# Mezzanine_Connectors.net
KiCad netlist of a schematic drawn in Altium Designer
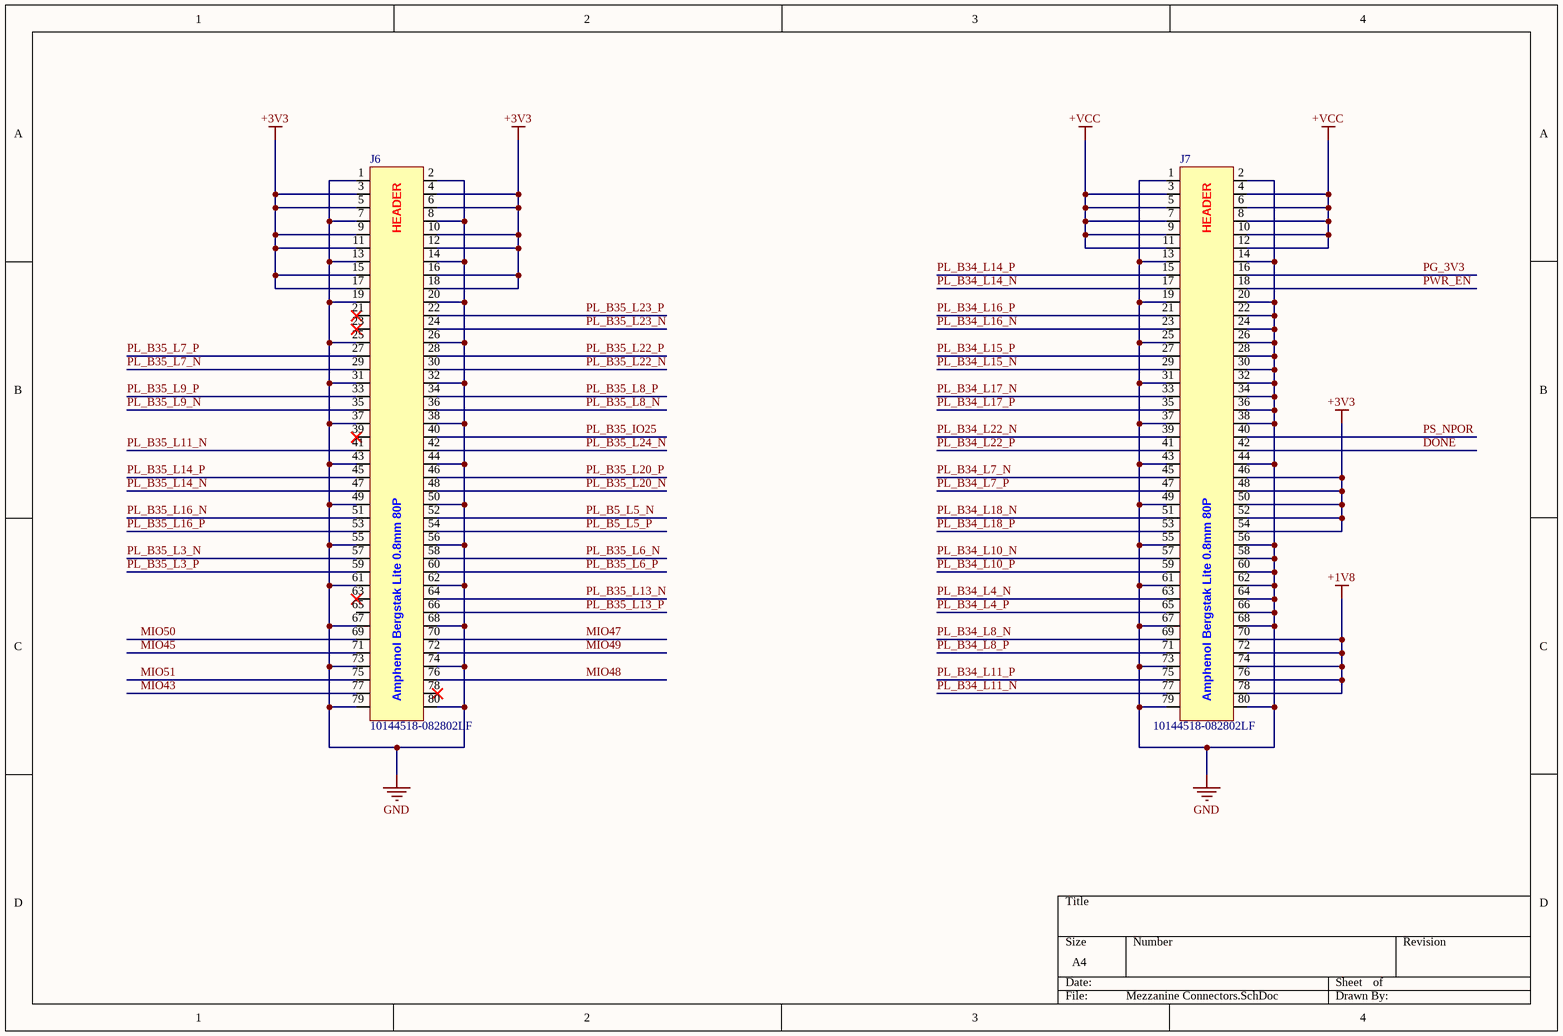
[diagram p0: Mezzanine Connectors.SchDoc]

(export (version "E")
  (design (tool "Eeschema 10.0.6"))
  (components
    (comp (ref "J6")
      (value "10144518-082802LF")
      (footprint "10144518-082802LF")
      (description "BergStak® Lite 0.80mm, Board-to-Board Connector, 80 Positions, Dual Row, Vertical Header")
      (fields (field (name "MANUFACTURER") "Amphenol"))
      (libsource (lib "Schematic-Lib-PhilsLab") (part "10144518-082802LF"))
    )
    (comp (ref "J7")
      (value "10144518-082802LF")
      (footprint "10144518-082802LF")
      (description "BergStak® Lite 0.80mm, Board-to-Board Connector, 80 Positions, Dual Row, Vertical Header")
      (fields (field (name "MANUFACTURER") "Amphenol"))
      (libsource (lib "Schematic-Lib-PhilsLab") (part "10144518-082802LF"))
    )
  )
  (nets
    (net (code "1") (name "+1V8") (class "Default")
      (node (ref "J7") (pin "70") (pintype "passive"))
      (node (ref "J7") (pin "72") (pintype "passive"))
      (node (ref "J7") (pin "74") (pintype "passive"))
      (node (ref "J7") (pin "76") (pintype "passive"))
      (node (ref "J7") (pin "78") (pintype "passive"))
    )
    (net (code "2") (name "+3V3") (class "Default")
      (node (ref "J6") (pin "10") (pintype "passive"))
      (node (ref "J6") (pin "11") (pintype "passive"))
      (node (ref "J6") (pin "12") (pintype "passive"))
      (node (ref "J6") (pin "15") (pintype "passive"))
      (node (ref "J6") (pin "16") (pintype "passive"))
      (node (ref "J6") (pin "17") (pintype "passive"))
      (node (ref "J6") (pin "18") (pintype "passive"))
      (node (ref "J6") (pin "3") (pintype "passive"))
      (node (ref "J6") (pin "4") (pintype "passive"))
      (node (ref "J6") (pin "5") (pintype "passive"))
      (node (ref "J6") (pin "6") (pintype "passive"))
      (node (ref "J6") (pin "9") (pintype "passive"))
      (node (ref "J7") (pin "46") (pintype "passive"))
      (node (ref "J7") (pin "48") (pintype "passive"))
      (node (ref "J7") (pin "50") (pintype "passive"))
      (node (ref "J7") (pin "52") (pintype "passive"))
      (node (ref "J7") (pin "54") (pintype "passive"))
    )
    (net (code "3") (name "+VCC") (class "Default")
      (node (ref "J7") (pin "10") (pintype "passive"))
      (node (ref "J7") (pin "11") (pintype "passive"))
      (node (ref "J7") (pin "12") (pintype "passive"))
      (node (ref "J7") (pin "3") (pintype "passive"))
      (node (ref "J7") (pin "4") (pintype "passive"))
      (node (ref "J7") (pin "5") (pintype "passive"))
      (node (ref "J7") (pin "6") (pintype "passive"))
      (node (ref "J7") (pin "7") (pintype "passive"))
      (node (ref "J7") (pin "8") (pintype "passive"))
      (node (ref "J7") (pin "9") (pintype "passive"))
    )
    (net (code "4") (name "/DONE") (class "Default") (node (ref "J7") (pin "42") (pintype "passive")))
    (net (code "5") (name "/MIO43") (class "Default") (node (ref "J6") (pin "77") (pintype "passive")))
    (net (code "6") (name "/MIO45") (class "Default") (node (ref "J6") (pin "71") (pintype "passive")))
    (net (code "7") (name "/MIO47") (class "Default") (node (ref "J6") (pin "70") (pintype "passive")))
    (net (code "8") (name "/MIO48") (class "Default") (node (ref "J6") (pin "76") (pintype "passive")))
    (net (code "9") (name "/MIO49") (class "Default") (node (ref "J6") (pin "72") (pintype "passive")))
    (net (code "10") (name "/MIO50") (class "Default") (node (ref "J6") (pin "69") (pintype "passive")))
    (net (code "11") (name "/MIO51") (class "Default") (node (ref "J6") (pin "75") (pintype "passive")))
    (net (code "12") (name "/PG_3V3") (class "Default") (node (ref "J7") (pin "16") (pintype "passive")))
    (net (code "13") (name "/PL_B5_L5_N") (class "Default") (node (ref "J6") (pin "52") (pintype "passive")))
    (net (code "14") (name "/PL_B5_L5_P") (class "Default") (node (ref "J6") (pin "54") (pintype "passive")))
    (net (code "15") (name "/PL_B34_L4_N") (class "Default") (node (ref "J7") (pin "63") (pintype "passive")))
    (net (code "16") (name "/PL_B34_L4_P") (class "Default") (node (ref "J7") (pin "65") (pintype "passive")))
    (net (code "17") (name "/PL_B34_L7_N") (class "Default") (node (ref "J7") (pin "45") (pintype "passive")))
    (net (code "18") (name "/PL_B34_L7_P") (class "Default") (node (ref "J7") (pin "47") (pintype "passive")))
    (net (code "19") (name "/PL_B34_L8_N") (class "Default") (node (ref "J7") (pin "69") (pintype "passive")))
    (net (code "20") (name "/PL_B34_L8_P") (class "Default") (node (ref "J7") (pin "71") (pintype "passive")))
    (net (code "21") (name "/PL_B34_L10_N") (class "Default")
      (node (ref "J7") (pin "57") (pintype "passive"))
    )
    (net (code "22") (name "/PL_B34_L10_P") (class "Default")
      (node (ref "J7") (pin "59") (pintype "passive"))
    )
    (net (code "23") (name "/PL_B34_L11_N") (class "Default")
      (node (ref "J7") (pin "77") (pintype "passive"))
    )
    (net (code "24") (name "/PL_B34_L11_P") (class "Default")
      (node (ref "J7") (pin "75") (pintype "passive"))
    )
    (net (code "25") (name "/PL_B34_L14_N") (class "Default")
      (node (ref "J7") (pin "17") (pintype "passive"))
    )
    (net (code "26") (name "/PL_B34_L14_P") (class "Default")
      (node (ref "J7") (pin "15") (pintype "passive"))
    )
    (net (code "27") (name "/PL_B34_L15_N") (class "Default")
      (node (ref "J7") (pin "29") (pintype "passive"))
    )
    (net (code "28") (name "/PL_B34_L15_P") (class "Default")
      (node (ref "J7") (pin "27") (pintype "passive"))
    )
    (net (code "29") (name "/PL_B34_L16_N") (class "Default")
      (node (ref "J7") (pin "23") (pintype "passive"))
    )
    (net (code "30") (name "/PL_B34_L16_P") (class "Default")
      (node (ref "J7") (pin "21") (pintype "passive"))
    )
    (net (code "31") (name "/PL_B34_L17_N") (class "Default")
      (node (ref "J7") (pin "33") (pintype "passive"))
    )
    (net (code "32") (name "/PL_B34_L17_P") (class "Default")
      (node (ref "J7") (pin "35") (pintype "passive"))
    )
    (net (code "33") (name "/PL_B34_L18_N") (class "Default")
      (node (ref "J7") (pin "51") (pintype "passive"))
    )
    (net (code "34") (name "/PL_B34_L18_P") (class "Default")
      (node (ref "J7") (pin "53") (pintype "passive"))
    )
    (net (code "35") (name "/PL_B34_L22_N") (class "Default")
      (node (ref "J7") (pin "39") (pintype "passive"))
    )
    (net (code "36") (name "/PL_B34_L22_P") (class "Default")
      (node (ref "J7") (pin "41") (pintype "passive"))
    )
    (net (code "37") (name "/PL_B35_IO25") (class "Default") (node (ref "J6") (pin "40") (pintype "passive")))
    (net (code "38") (name "/PL_B35_L3_N") (class "Default") (node (ref "J6") (pin "57") (pintype "passive")))
    (net (code "39") (name "/PL_B35_L3_P") (class "Default") (node (ref "J6") (pin "59") (pintype "passive")))
    (net (code "40") (name "/PL_B35_L6_N") (class "Default") (node (ref "J6") (pin "58") (pintype "passive")))
    (net (code "41") (name "/PL_B35_L6_P") (class "Default") (node (ref "J6") (pin "60") (pintype "passive")))
    (net (code "42") (name "/PL_B35_L7_N") (class "Default") (node (ref "J6") (pin "29") (pintype "passive")))
    (net (code "43") (name "/PL_B35_L7_P") (class "Default") (node (ref "J6") (pin "27") (pintype "passive")))
    (net (code "44") (name "/PL_B35_L8_N") (class "Default") (node (ref "J6") (pin "36") (pintype "passive")))
    (net (code "45") (name "/PL_B35_L8_P") (class "Default") (node (ref "J6") (pin "34") (pintype "passive")))
    (net (code "46") (name "/PL_B35_L9_N") (class "Default") (node (ref "J6") (pin "35") (pintype "passive")))
    (net (code "47") (name "/PL_B35_L9_P") (class "Default") (node (ref "J6") (pin "33") (pintype "passive")))
    (net (code "48") (name "/PL_B35_L11_N") (class "Default")
      (node (ref "J6") (pin "41") (pintype "passive"))
    )
    (net (code "49") (name "/PL_B35_L13_N") (class "Default")
      (node (ref "J6") (pin "64") (pintype "passive"))
    )
    (net (code "50") (name "/PL_B35_L13_P") (class "Default")
      (node (ref "J6") (pin "66") (pintype "passive"))
    )
    (net (code "51") (name "/PL_B35_L14_N") (class "Default")
      (node (ref "J6") (pin "47") (pintype "passive"))
    )
    (net (code "52") (name "/PL_B35_L14_P") (class "Default")
      (node (ref "J6") (pin "45") (pintype "passive"))
    )
    (net (code "53") (name "/PL_B35_L16_N") (class "Default")
      (node (ref "J6") (pin "51") (pintype "passive"))
    )
    (net (code "54") (name "/PL_B35_L16_P") (class "Default")
      (node (ref "J6") (pin "53") (pintype "passive"))
    )
    (net (code "55") (name "/PL_B35_L20_N") (class "Default")
      (node (ref "J6") (pin "48") (pintype "passive"))
    )
    (net (code "56") (name "/PL_B35_L20_P") (class "Default")
      (node (ref "J6") (pin "46") (pintype "passive"))
    )
    (net (code "57") (name "/PL_B35_L22_N") (class "Default")
      (node (ref "J6") (pin "30") (pintype "passive"))
    )
    (net (code "58") (name "/PL_B35_L22_P") (class "Default")
      (node (ref "J6") (pin "28") (pintype "passive"))
    )
    (net (code "59") (name "/PL_B35_L23_N") (class "Default")
      (node (ref "J6") (pin "24") (pintype "passive"))
    )
    (net (code "60") (name "/PL_B35_L23_P") (class "Default")
      (node (ref "J6") (pin "22") (pintype "passive"))
    )
    (net (code "61") (name "/PL_B35_L24_N") (class "Default")
      (node (ref "J6") (pin "42") (pintype "passive"))
    )
    (net (code "62") (name "/PS_NPOR") (class "Default") (node (ref "J7") (pin "40") (pintype "passive")))
    (net (code "63") (name "/PWR_EN") (class "Default") (node (ref "J7") (pin "18") (pintype "passive")))
    (net (code "64") (name "GND") (class "Default")
      (node (ref "J6") (pin "1") (pintype "passive"))
      (node (ref "J6") (pin "13") (pintype "passive"))
      (node (ref "J6") (pin "14") (pintype "passive"))
      (node (ref "J6") (pin "19") (pintype "passive"))
      (node (ref "J6") (pin "2") (pintype "passive"))
      (node (ref "J6") (pin "20") (pintype "passive"))
      (node (ref "J6") (pin "25") (pintype "passive"))
      (node (ref "J6") (pin "26") (pintype "passive"))
      (node (ref "J6") (pin "31") (pintype "passive"))
      (node (ref "J6") (pin "32") (pintype "passive"))
      (node (ref "J6") (pin "37") (pintype "passive"))
      (node (ref "J6") (pin "38") (pintype "passive"))
      (node (ref "J6") (pin "43") (pintype "passive"))
      (node (ref "J6") (pin "44") (pintype "passive"))
      (node (ref "J6") (pin "49") (pintype "passive"))
      (node (ref "J6") (pin "50") (pintype "passive"))
      (node (ref "J6") (pin "55") (pintype "passive"))
      (node (ref "J6") (pin "56") (pintype "passive"))
      (node (ref "J6") (pin "61") (pintype "passive"))
      (node (ref "J6") (pin "62") (pintype "passive"))
      (node (ref "J6") (pin "67") (pintype "passive"))
      (node (ref "J6") (pin "68") (pintype "passive"))
      (node (ref "J6") (pin "7") (pintype "passive"))
      (node (ref "J6") (pin "73") (pintype "passive"))
      (node (ref "J6") (pin "74") (pintype "passive"))
      (node (ref "J6") (pin "79") (pintype "passive"))
      (node (ref "J6") (pin "8") (pintype "passive"))
      (node (ref "J6") (pin "80") (pintype "passive"))
      (node (ref "J7") (pin "1") (pintype "passive"))
      (node (ref "J7") (pin "13") (pintype "passive"))
      (node (ref "J7") (pin "14") (pintype "passive"))
      (node (ref "J7") (pin "19") (pintype "passive"))
      (node (ref "J7") (pin "2") (pintype "passive"))
      (node (ref "J7") (pin "20") (pintype "passive"))
      (node (ref "J7") (pin "22") (pintype "passive"))
      (node (ref "J7") (pin "24") (pintype "passive"))
      (node (ref "J7") (pin "25") (pintype "passive"))
      (node (ref "J7") (pin "26") (pintype "passive"))
      (node (ref "J7") (pin "28") (pintype "passive"))
      (node (ref "J7") (pin "30") (pintype "passive"))
      (node (ref "J7") (pin "31") (pintype "passive"))
      (node (ref "J7") (pin "32") (pintype "passive"))
      (node (ref "J7") (pin "34") (pintype "passive"))
      (node (ref "J7") (pin "36") (pintype "passive"))
      (node (ref "J7") (pin "37") (pintype "passive"))
      (node (ref "J7") (pin "38") (pintype "passive"))
      (node (ref "J7") (pin "43") (pintype "passive"))
      (node (ref "J7") (pin "44") (pintype "passive"))
      (node (ref "J7") (pin "49") (pintype "passive"))
      (node (ref "J7") (pin "55") (pintype "passive"))
      (node (ref "J7") (pin "56") (pintype "passive"))
      (node (ref "J7") (pin "58") (pintype "passive"))
      (node (ref "J7") (pin "60") (pintype "passive"))
      (node (ref "J7") (pin "61") (pintype "passive"))
      (node (ref "J7") (pin "62") (pintype "passive"))
      (node (ref "J7") (pin "64") (pintype "passive"))
      (node (ref "J7") (pin "66") (pintype "passive"))
      (node (ref "J7") (pin "67") (pintype "passive"))
      (node (ref "J7") (pin "68") (pintype "passive"))
      (node (ref "J7") (pin "73") (pintype "passive"))
      (node (ref "J7") (pin "79") (pintype "passive"))
      (node (ref "J7") (pin "80") (pintype "passive"))
    )
    (net (code "65") (name "unconnected-(J6-Pad21)") (class "Default")
      (node (ref "J6") (pin "21") (pintype "passive+no_connect"))
    )
    (net (code "66") (name "unconnected-(J6-Pad23)") (class "Default")
      (node (ref "J6") (pin "23") (pintype "passive+no_connect"))
    )
    (net (code "67") (name "unconnected-(J6-Pad39)") (class "Default")
      (node (ref "J6") (pin "39") (pintype "passive+no_connect"))
    )
    (net (code "68") (name "unconnected-(J6-Pad63)") (class "Default")
      (node (ref "J6") (pin "63") (pintype "passive+no_connect"))
    )
    (net (code "69") (name "unconnected-(J6-Pad65)") (class "Default")
      (node (ref "J6") (pin "65") (pintype "passive"))
    )
    (net (code "70") (name "unconnected-(J6-Pad78)") (class "Default")
      (node (ref "J6") (pin "78") (pintype "passive+no_connect"))
    )
  )
)
